# 2_comp_stage.net
KiCad netlist of a schematic drawn in Altium Designer
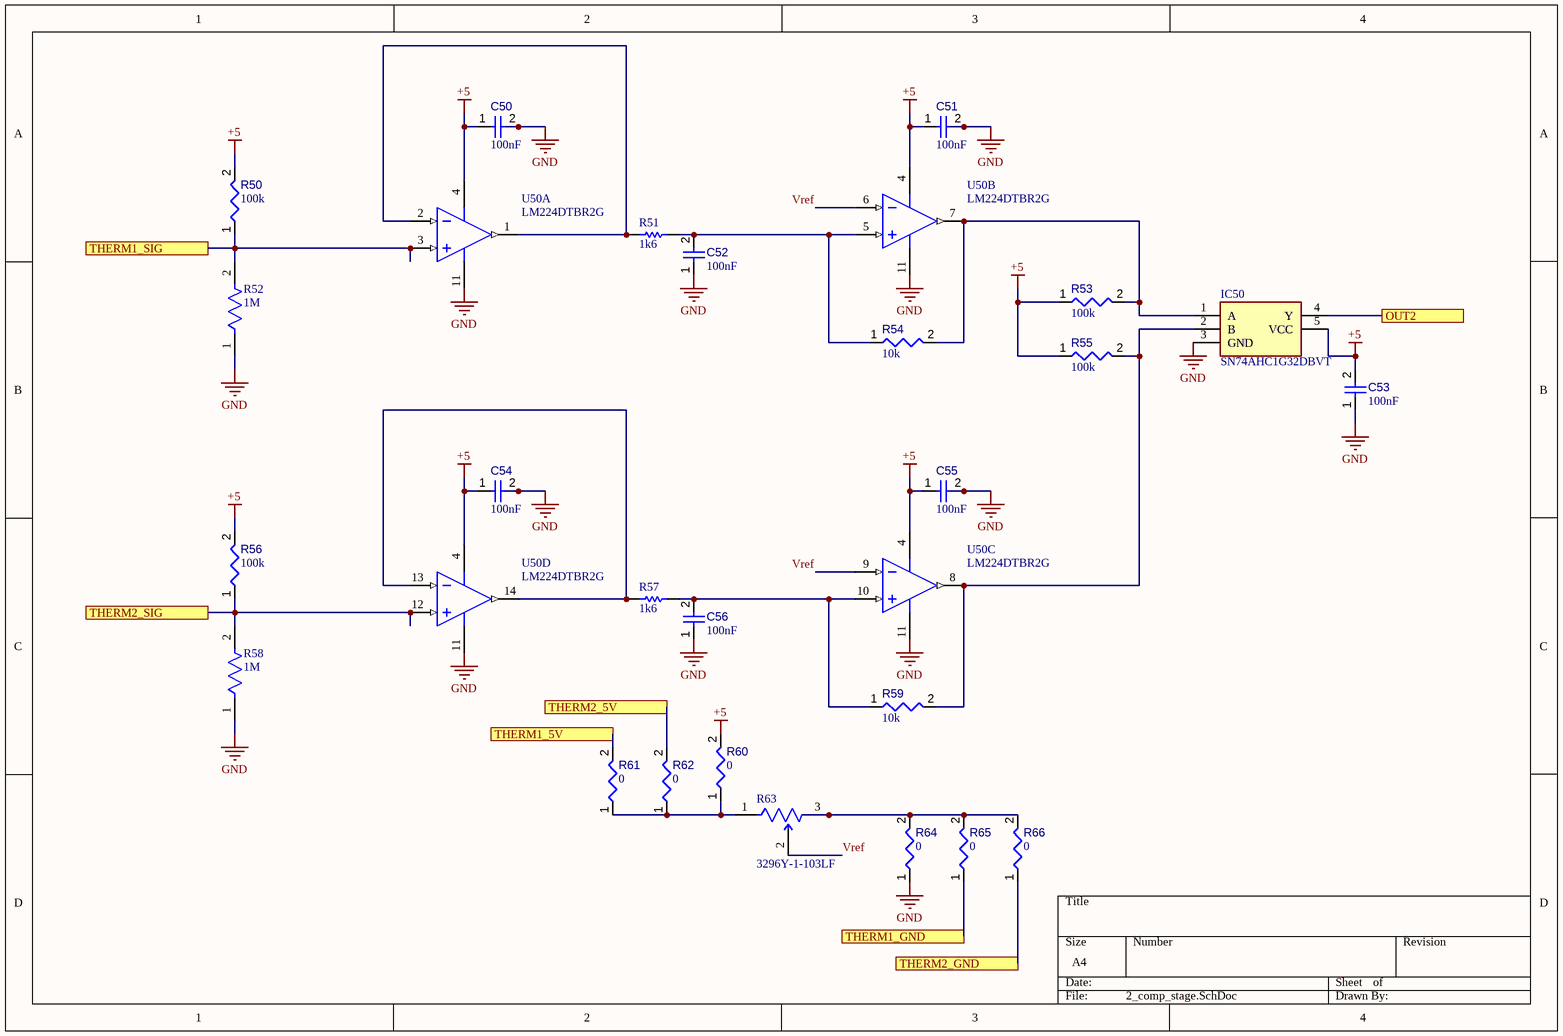
[diagram p0: 2_comp_stage.SchDoc]

(export (version "E")
  (design (tool "Eeschema 10.0.6"))
  (components
    (comp (ref "C50")
      (value "100nF")
      (footprint "CAPC1608X90X40NL10T20")
      (description "Chip Capacitor, 100 nF, +/- 10%, 50 V, 0603 (1608 Metric)")
      (fields (field (name "TOLERANCE") "10%") (field (name "Comment") "Capacitor 100 nF +/-10% 50 V 0603"))
      (libsource (lib "UNSW Redback Racing") (part "CAP-NP-2"))
    )
    (comp (ref "C51")
      (value "100nF")
      (footprint "CAPC1608X90X40NL10T20")
      (description "Chip Capacitor, 100 nF, +/- 10%, 50 V, 0603 (1608 Metric)")
      (fields (field (name "TOLERANCE") "10%") (field (name "Comment") "Capacitor 100 nF +/-10% 50 V 0603"))
      (libsource (lib "UNSW Redback Racing") (part "CAP-NP-2"))
    )
    (comp (ref "C52")
      (value "100nF")
      (footprint "CAPC1608X90X40NL10T20")
      (description "Chip Capacitor, 100 nF, +/- 10%, 50 V, 0603 (1608 Metric)")
      (fields (field (name "TOLERANCE") "10%") (field (name "Comment") "Capacitor 100 nF +/-10% 50 V 0603"))
      (libsource (lib "UNSW Redback Racing") (part "CAP-NP-2"))
    )
    (comp (ref "C53")
      (value "100nF")
      (footprint "CAPC1608X90X40NL10T20")
      (description "Chip Capacitor, 100 nF, +/- 10%, 50 V, 0603 (1608 Metric)")
      (fields (field (name "TOLERANCE") "10%") (field (name "Comment") "Capacitor 100 nF +/-10% 50 V 0603"))
      (libsource (lib "UNSW Redback Racing") (part "CAP-NP-2"))
    )
    (comp (ref "C54")
      (value "100nF")
      (footprint "CAPC1608X90X40NL10T20")
      (description "Chip Capacitor, 100 nF, +/- 10%, 50 V, 0603 (1608 Metric)")
      (fields (field (name "TOLERANCE") "10%") (field (name "Comment") "Capacitor 100 nF +/-10% 50 V 0603"))
      (libsource (lib "UNSW Redback Racing") (part "CAP-NP-2"))
    )
    (comp (ref "C55")
      (value "100nF")
      (footprint "CAPC1608X90X40NL10T20")
      (description "Chip Capacitor, 100 nF, +/- 10%, 50 V, 0603 (1608 Metric)")
      (fields (field (name "TOLERANCE") "10%") (field (name "Comment") "Capacitor 100 nF +/-10% 50 V 0603"))
      (libsource (lib "UNSW Redback Racing") (part "CAP-NP-2"))
    )
    (comp (ref "C56")
      (value "100nF")
      (footprint "CAPC1608X90X40NL10T20")
      (description "Chip Capacitor, 100 nF, +/- 10%, 50 V, 0603 (1608 Metric)")
      (fields (field (name "TOLERANCE") "10%") (field (name "Comment") "Capacitor 100 nF +/-10% 50 V 0603"))
      (libsource (lib "UNSW Redback Racing") (part "CAP-NP-2"))
    )
    (comp (ref "IC50")
      (value "SN74AHC1G32DBVT")
      (footprint "SamacSys:SOT95P280X145-5N")
      (description "Integrated Circuit")
      (fields (field (name "MOUSER PART NUMBER") "595-SN74AHC1G32DBVT"))
      (libsource (lib "*") (part "SN74AHC1G32DBVT"))
    )
    (comp (ref "R50")
      (value "100k")
      (footprint "RESC1608X55X25ML10T15")
      (description "Chip Resistor, 100 KOhm, +/- 1%, 0.1 W, -55 to 155 degC, 0603 (1608 Metric)")
      (fields (field (name "TOLERANCE") "1%") (field (name "POWER") "100mW"))
      (libsource (lib "UNSW Redback Racing") (part "RES-2"))
    )
    (comp (ref "R51")
      (value "1k6")
      (footprint "RESC1609X50X30LL10T20")
      (fields (field (name "PART NUMBER") "CRCW06031K60FKEA") (field (name "MANUFACTURER") "Vishay Dale"))
      (libsource (lib "Altium Content Vault") (part "RES"))
    )
    (comp (ref "R52")
      (value "1M")
      (footprint "FP-RMCF0603-IPC_B")
      (description "1MΩ ±1% 0.1W 0603 Thick Film Chip Resistor AEC-Q200 compliant")
      (fields (field (name "TOLERANCE") "1%"))
      (libsource (lib "Altium Content Vault") (part "1029c3af85768c4190bb7ad29bc67b5"))
    )
    (comp (ref "R53")
      (value "100k")
      (footprint "RESC1608X55X25ML10T15")
      (description "Chip Resistor, 100 KOhm, +/- 1%, 0.1 W, -55 to 155 degC, 0603 (1608 Metric)")
      (fields (field (name "TOLERANCE") "1%") (field (name "POWER") "100mW"))
      (libsource (lib "UNSW Redback Racing") (part "RES-2"))
    )
    (comp (ref "R54")
      (value "10k")
      (footprint "RESC1608X55X25ML10T15")
      (description "Chip Resistor, 10 KOhm, +/- 1%, 01 W, -55 to 155 degC, 0603 (1608 Metric)")
      (fields (field (name "POWER") "100mW") (field (name "TOLERANCE") "1%"))
      (libsource (lib "UNSW Redback Racing") (part "RES-2"))
    )
    (comp (ref "R55")
      (value "100k")
      (footprint "RESC1608X55X25ML10T15")
      (description "Chip Resistor, 100 KOhm, +/- 1%, 0.1 W, -55 to 155 degC, 0603 (1608 Metric)")
      (fields (field (name "TOLERANCE") "1%") (field (name "POWER") "100mW"))
      (libsource (lib "UNSW Redback Racing") (part "RES-2"))
    )
    (comp (ref "R56")
      (value "100k")
      (footprint "RESC1608X55X25ML10T15")
      (description "Chip Resistor, 100 KOhm, +/- 1%, 0.1 W, -55 to 155 degC, 0603 (1608 Metric)")
      (fields (field (name "TOLERANCE") "1%") (field (name "POWER") "100mW"))
      (libsource (lib "UNSW Redback Racing") (part "RES-2"))
    )
    (comp (ref "R57")
      (value "1k6")
      (footprint "RESC1609X50X30LL10T20")
      (fields (field (name "PART NUMBER") "CRCW06031K60FKEA") (field (name "MANUFACTURER") "Vishay Dale"))
      (libsource (lib "Altium Content Vault") (part "RES"))
    )
    (comp (ref "R58")
      (value "1M")
      (footprint "FP-RMCF0603-IPC_B")
      (description "1MΩ ±1% 0.1W 0603 Thick Film Chip Resistor AEC-Q200 compliant")
      (fields (field (name "TOLERANCE") "1%"))
      (libsource (lib "Altium Content Vault") (part "1029c3af85768c4190bb7ad29bc67b5"))
    )
    (comp (ref "R59")
      (value "10k")
      (footprint "RESC1608X55X25ML10T15")
      (description "Chip Resistor, 10 KOhm, +/- 1%, 01 W, -55 to 155 degC, 0603 (1608 Metric)")
      (fields (field (name "POWER") "100mW") (field (name "TOLERANCE") "1%"))
      (libsource (lib "UNSW Redback Racing") (part "RES-2"))
    )
    (comp (ref "R60")
      (value "0")
      (footprint "RESC0603(1608)_L")
      (description "Jumper 0603 (1608 Metric)")
      (fields (field (name "Comment") "0R3J"))
      (libsource (lib "UNSW Redback Racing") (part "0R3J"))
    )
    (comp (ref "R61")
      (value "0")
      (footprint "RESC0603(1608)_L")
      (description "Jumper 0603 (1608 Metric)")
      (fields (field (name "Comment") "0R3J"))
      (libsource (lib "UNSW Redback Racing") (part "0R3J"))
    )
    (comp (ref "R62")
      (value "0")
      (footprint "RESC0603(1608)_L")
      (description "Jumper 0603 (1608 Metric)")
      (fields (field (name "Comment") "0R3J"))
      (libsource (lib "UNSW Redback Racing") (part "0R3J"))
    )
    (comp (ref "R63")
      (value "3296Y-1-103LF")
      (footprint "FP-3296Y-MFG")
      (description "TRIMMER 10K OHM 0.5W PC PIN TOP")
      (fields (field (name "TOLERANCE") "10%"))
      (libsource (lib "Altium Content Vault") (part "2dcfd2547301a7d3209a5e99acfd772"))
    )
    (comp (ref "R64")
      (value "0")
      (footprint "RESC0603(1608)_L")
      (description "Jumper 0603 (1608 Metric)")
      (fields (field (name "Comment") "0R3J"))
      (libsource (lib "UNSW Redback Racing") (part "0R3J"))
    )
    (comp (ref "R65")
      (value "0")
      (footprint "RESC0603(1608)_L")
      (description "Jumper 0603 (1608 Metric)")
      (fields (field (name "Comment") "0R3J"))
      (libsource (lib "UNSW Redback Racing") (part "0R3J"))
    )
    (comp (ref "R66")
      (value "0")
      (footprint "RESC0603(1608)_L")
      (description "Jumper 0603 (1608 Metric)")
      (fields (field (name "Comment") "0R3J"))
      (libsource (lib "UNSW Redback Racing") (part "0R3J"))
    )
    (comp (ref "U50")
      (value "LM224DTBR2G")
      (footprint "ONSC-TSSOP-14-948G-01_V")
      (fields (field (name "MANUFACTURER") "On Semiconductor"))
      (libsource (lib "Altium Content Vault") (part "ONSC-LM224_324_2902_NCV2902-14"))
    )
  )
  (nets
    (net (code "1") (name "+5") (class "Default")
      (node (ref "C50") (pin "1") (pinfunction "1_1") (pintype "passive"))
      (node (ref "C51") (pin "1") (pinfunction "1_1") (pintype "passive"))
      (node (ref "C53") (pin "2") (pinfunction "2_2") (pintype "passive"))
      (node (ref "C54") (pin "1") (pinfunction "1_1") (pintype "passive"))
      (node (ref "C55") (pin "1") (pinfunction "1_1") (pintype "passive"))
      (node (ref "IC50") (pin "5") (pinfunction "VCC_5") (pintype "passive"))
      (node (ref "R50") (pin "2") (pinfunction "2_2") (pintype "passive"))
      (node (ref "R53") (pin "1") (pinfunction "1_1") (pintype "passive"))
      (node (ref "R55") (pin "1") (pinfunction "1_1") (pintype "passive"))
      (node (ref "R56") (pin "2") (pinfunction "2_2") (pintype "passive"))
      (node (ref "R60") (pin "2") (pinfunction "2_2") (pintype "passive"))
      (node (ref "U50") (pin "4") (pinfunction "VCC_4") (pintype "power_in"))
    )
    (net (code "2") (name "/OUT2") (class "Default")
      (node (ref "IC50") (pin "4") (pinfunction "Y_4") (pintype "passive"))
    )
    (net (code "3") (name "/THERM1_5V") (class "Default")
      (node (ref "R61") (pin "2") (pinfunction "2_2") (pintype "passive"))
    )
    (net (code "4") (name "/THERM1_GND") (class "Default")
      (node (ref "R65") (pin "1") (pinfunction "1_1") (pintype "passive"))
    )
    (net (code "5") (name "/THERM1_SIG") (class "Default")
      (node (ref "R50") (pin "1") (pinfunction "1_1") (pintype "passive"))
      (node (ref "R52") (pin "2") (pinfunction "2_2") (pintype "passive"))
      (node (ref "U50") (pin "3") (pinfunction "IN1+_3") (pintype "input"))
    )
    (net (code "6") (name "/THERM2_5V") (class "Default")
      (node (ref "R62") (pin "2") (pinfunction "2_2") (pintype "passive"))
    )
    (net (code "7") (name "/THERM2_GND") (class "Default")
      (node (ref "R66") (pin "1") (pinfunction "1_1") (pintype "passive"))
    )
    (net (code "8") (name "/THERM2_SIG") (class "Default")
      (node (ref "R56") (pin "1") (pinfunction "1_1") (pintype "passive"))
      (node (ref "R58") (pin "2") (pinfunction "2_2") (pintype "passive"))
      (node (ref "U50") (pin "12") (pinfunction "IN4+_12") (pintype "input"))
    )
    (net (code "9") (name "/Vref") (class "Default")
      (node (ref "R63") (pin "2") (pinfunction "WIPER_2") (pintype "passive"))
      (node (ref "U50") (pin "6") (pinfunction "IN2-_6") (pintype "input"))
      (node (ref "U50") (pin "9") (pinfunction "IN3-_9") (pintype "input"))
    )
    (net (code "10") (name "GND") (class "Default")
      (node (ref "C50") (pin "2") (pinfunction "2_2") (pintype "passive"))
      (node (ref "C51") (pin "2") (pinfunction "2_2") (pintype "passive"))
      (node (ref "C52") (pin "1") (pinfunction "1_1") (pintype "passive"))
      (node (ref "C53") (pin "1") (pinfunction "1_1") (pintype "passive"))
      (node (ref "C54") (pin "2") (pinfunction "2_2") (pintype "passive"))
      (node (ref "C55") (pin "2") (pinfunction "2_2") (pintype "passive"))
      (node (ref "C56") (pin "1") (pinfunction "1_1") (pintype "passive"))
      (node (ref "IC50") (pin "3") (pinfunction "GND_3") (pintype "passive"))
      (node (ref "R52") (pin "1") (pinfunction "1_1") (pintype "passive"))
      (node (ref "R58") (pin "1") (pinfunction "1_1") (pintype "passive"))
      (node (ref "R64") (pin "1") (pinfunction "1_1") (pintype "passive"))
      (node (ref "U50") (pin "11") (pinfunction "VEE/GND_11") (pintype "power_in"))
    )
    (net (code "11") (name "Net-(IC50-A)") (class "Default")
      (node (ref "IC50") (pin "1") (pinfunction "A_1") (pintype "passive"))
      (node (ref "R53") (pin "2") (pinfunction "2_2") (pintype "passive"))
      (node (ref "R54") (pin "2") (pinfunction "2_2") (pintype "passive"))
      (node (ref "U50") (pin "7") (pinfunction "OUT2_7") (pintype "output"))
    )
    (net (code "12") (name "Net-(IC50-B)") (class "Default")
      (node (ref "IC50") (pin "2") (pinfunction "B_2") (pintype "passive"))
      (node (ref "R55") (pin "2") (pinfunction "2_2") (pintype "passive"))
      (node (ref "R59") (pin "2") (pinfunction "2_2") (pintype "passive"))
      (node (ref "U50") (pin "8") (pinfunction "OUT3_8") (pintype "output"))
    )
    (net (code "13") (name "Net-(R63-CCW)") (class "Default")
      (node (ref "R60") (pin "1") (pinfunction "1_1") (pintype "passive"))
      (node (ref "R61") (pin "1") (pinfunction "1_1") (pintype "passive"))
      (node (ref "R62") (pin "1") (pinfunction "1_1") (pintype "passive"))
      (node (ref "R63") (pin "1") (pinfunction "CCW_1") (pintype "passive"))
    )
    (net (code "14") (name "Net-(R63-CW)") (class "Default")
      (node (ref "R63") (pin "3") (pinfunction "CW_3") (pintype "passive"))
      (node (ref "R64") (pin "2") (pinfunction "2_2") (pintype "passive"))
      (node (ref "R65") (pin "2") (pinfunction "2_2") (pintype "passive"))
      (node (ref "R66") (pin "2") (pinfunction "2_2") (pintype "passive"))
    )
    (net (code "15") (name "Net-(U50A-IN1-)") (class "Default")
      (node (ref "R51") (pin "1") (pinfunction "1_1") (pintype "passive"))
      (node (ref "U50") (pin "1") (pinfunction "OUT1_1") (pintype "output"))
      (node (ref "U50") (pin "2") (pinfunction "IN1-_2") (pintype "input"))
    )
    (net (code "16") (name "Net-(U50B-IN2+)") (class "Default")
      (node (ref "C52") (pin "2") (pinfunction "2_2") (pintype "passive"))
      (node (ref "R51") (pin "2") (pinfunction "2_2") (pintype "passive"))
      (node (ref "R54") (pin "1") (pinfunction "1_1") (pintype "passive"))
      (node (ref "U50") (pin "5") (pinfunction "IN2+_5") (pintype "input"))
    )
    (net (code "17") (name "Net-(U50C-IN3+)") (class "Default")
      (node (ref "C56") (pin "2") (pinfunction "2_2") (pintype "passive"))
      (node (ref "R57") (pin "2") (pinfunction "2_2") (pintype "passive"))
      (node (ref "R59") (pin "1") (pinfunction "1_1") (pintype "passive"))
      (node (ref "U50") (pin "10") (pinfunction "IN3+_10") (pintype "input"))
    )
    (net (code "18") (name "Net-(U50D-IN4-)") (class "Default")
      (node (ref "R57") (pin "1") (pinfunction "1_1") (pintype "passive"))
      (node (ref "U50") (pin "13") (pinfunction "IN4-_13") (pintype "input"))
      (node (ref "U50") (pin "14") (pinfunction "OUT4_14") (pintype "output"))
    )
  )
)
